# C-07_PWR_MGR.net
KiCad netlist of a schematic drawn in Altium Designer
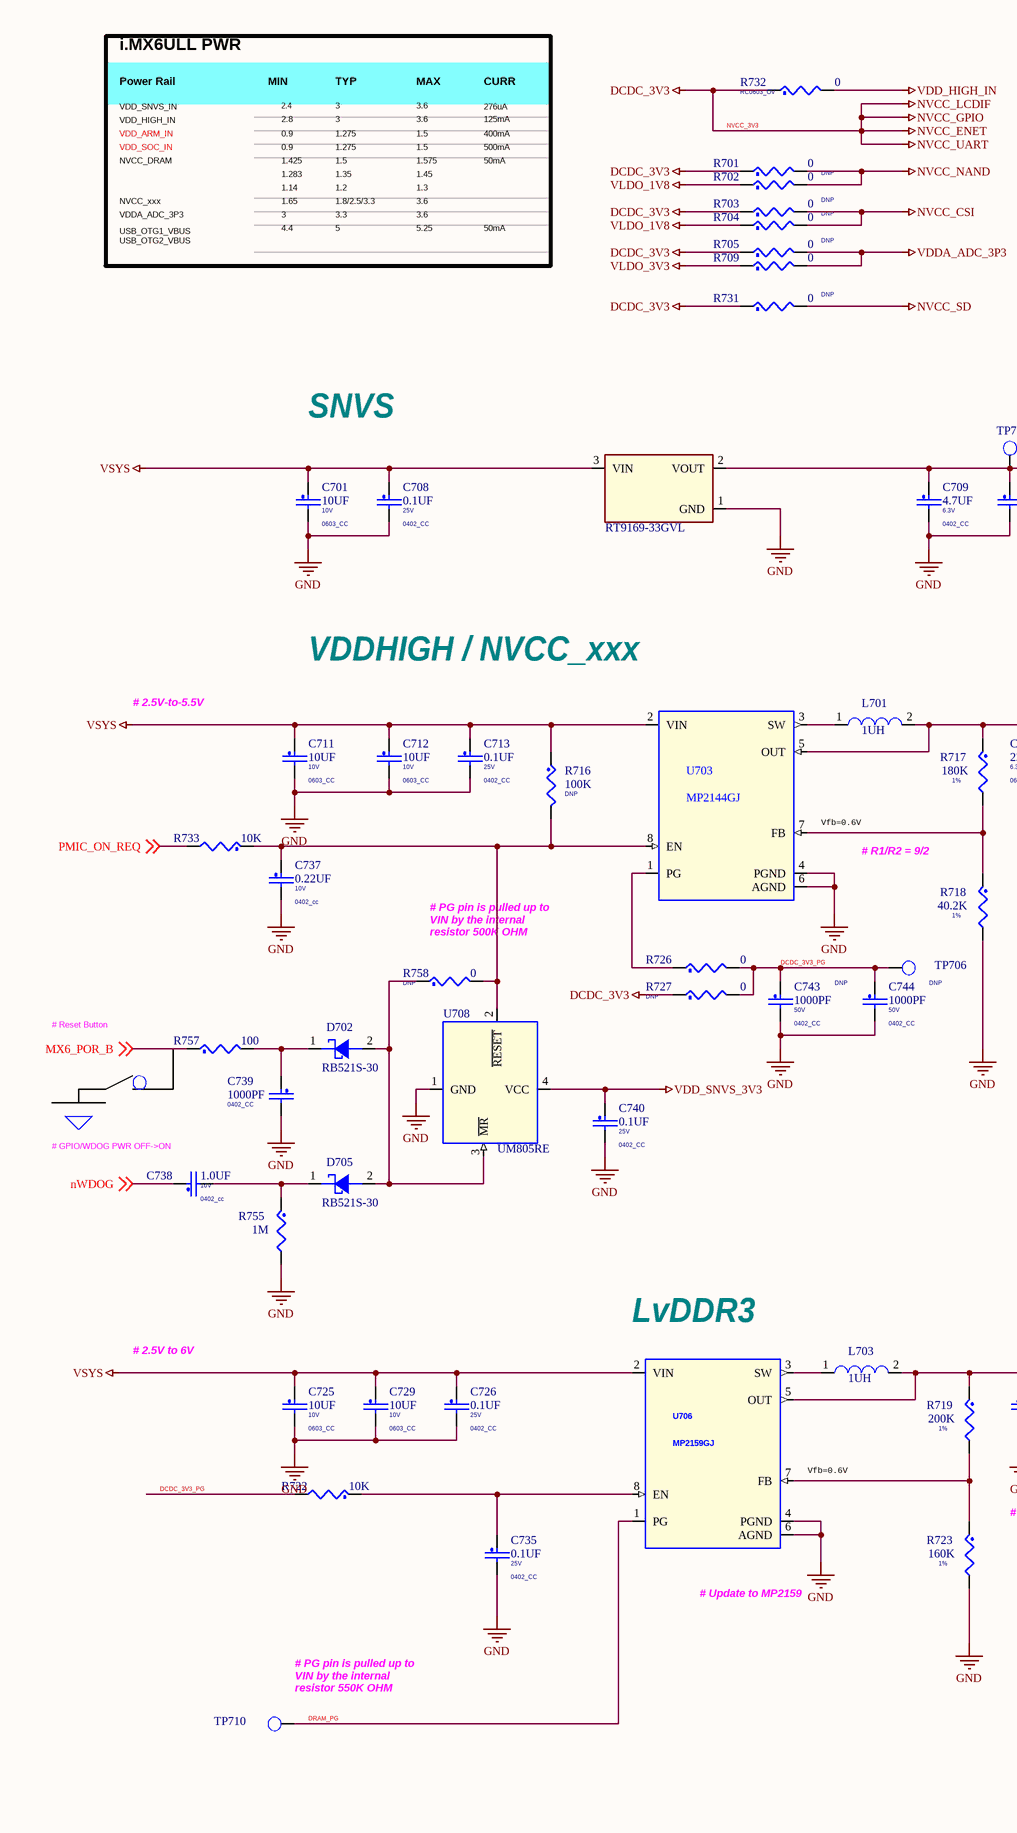
[diagram p0: C-07 PWR MGR.SchDoc, left]
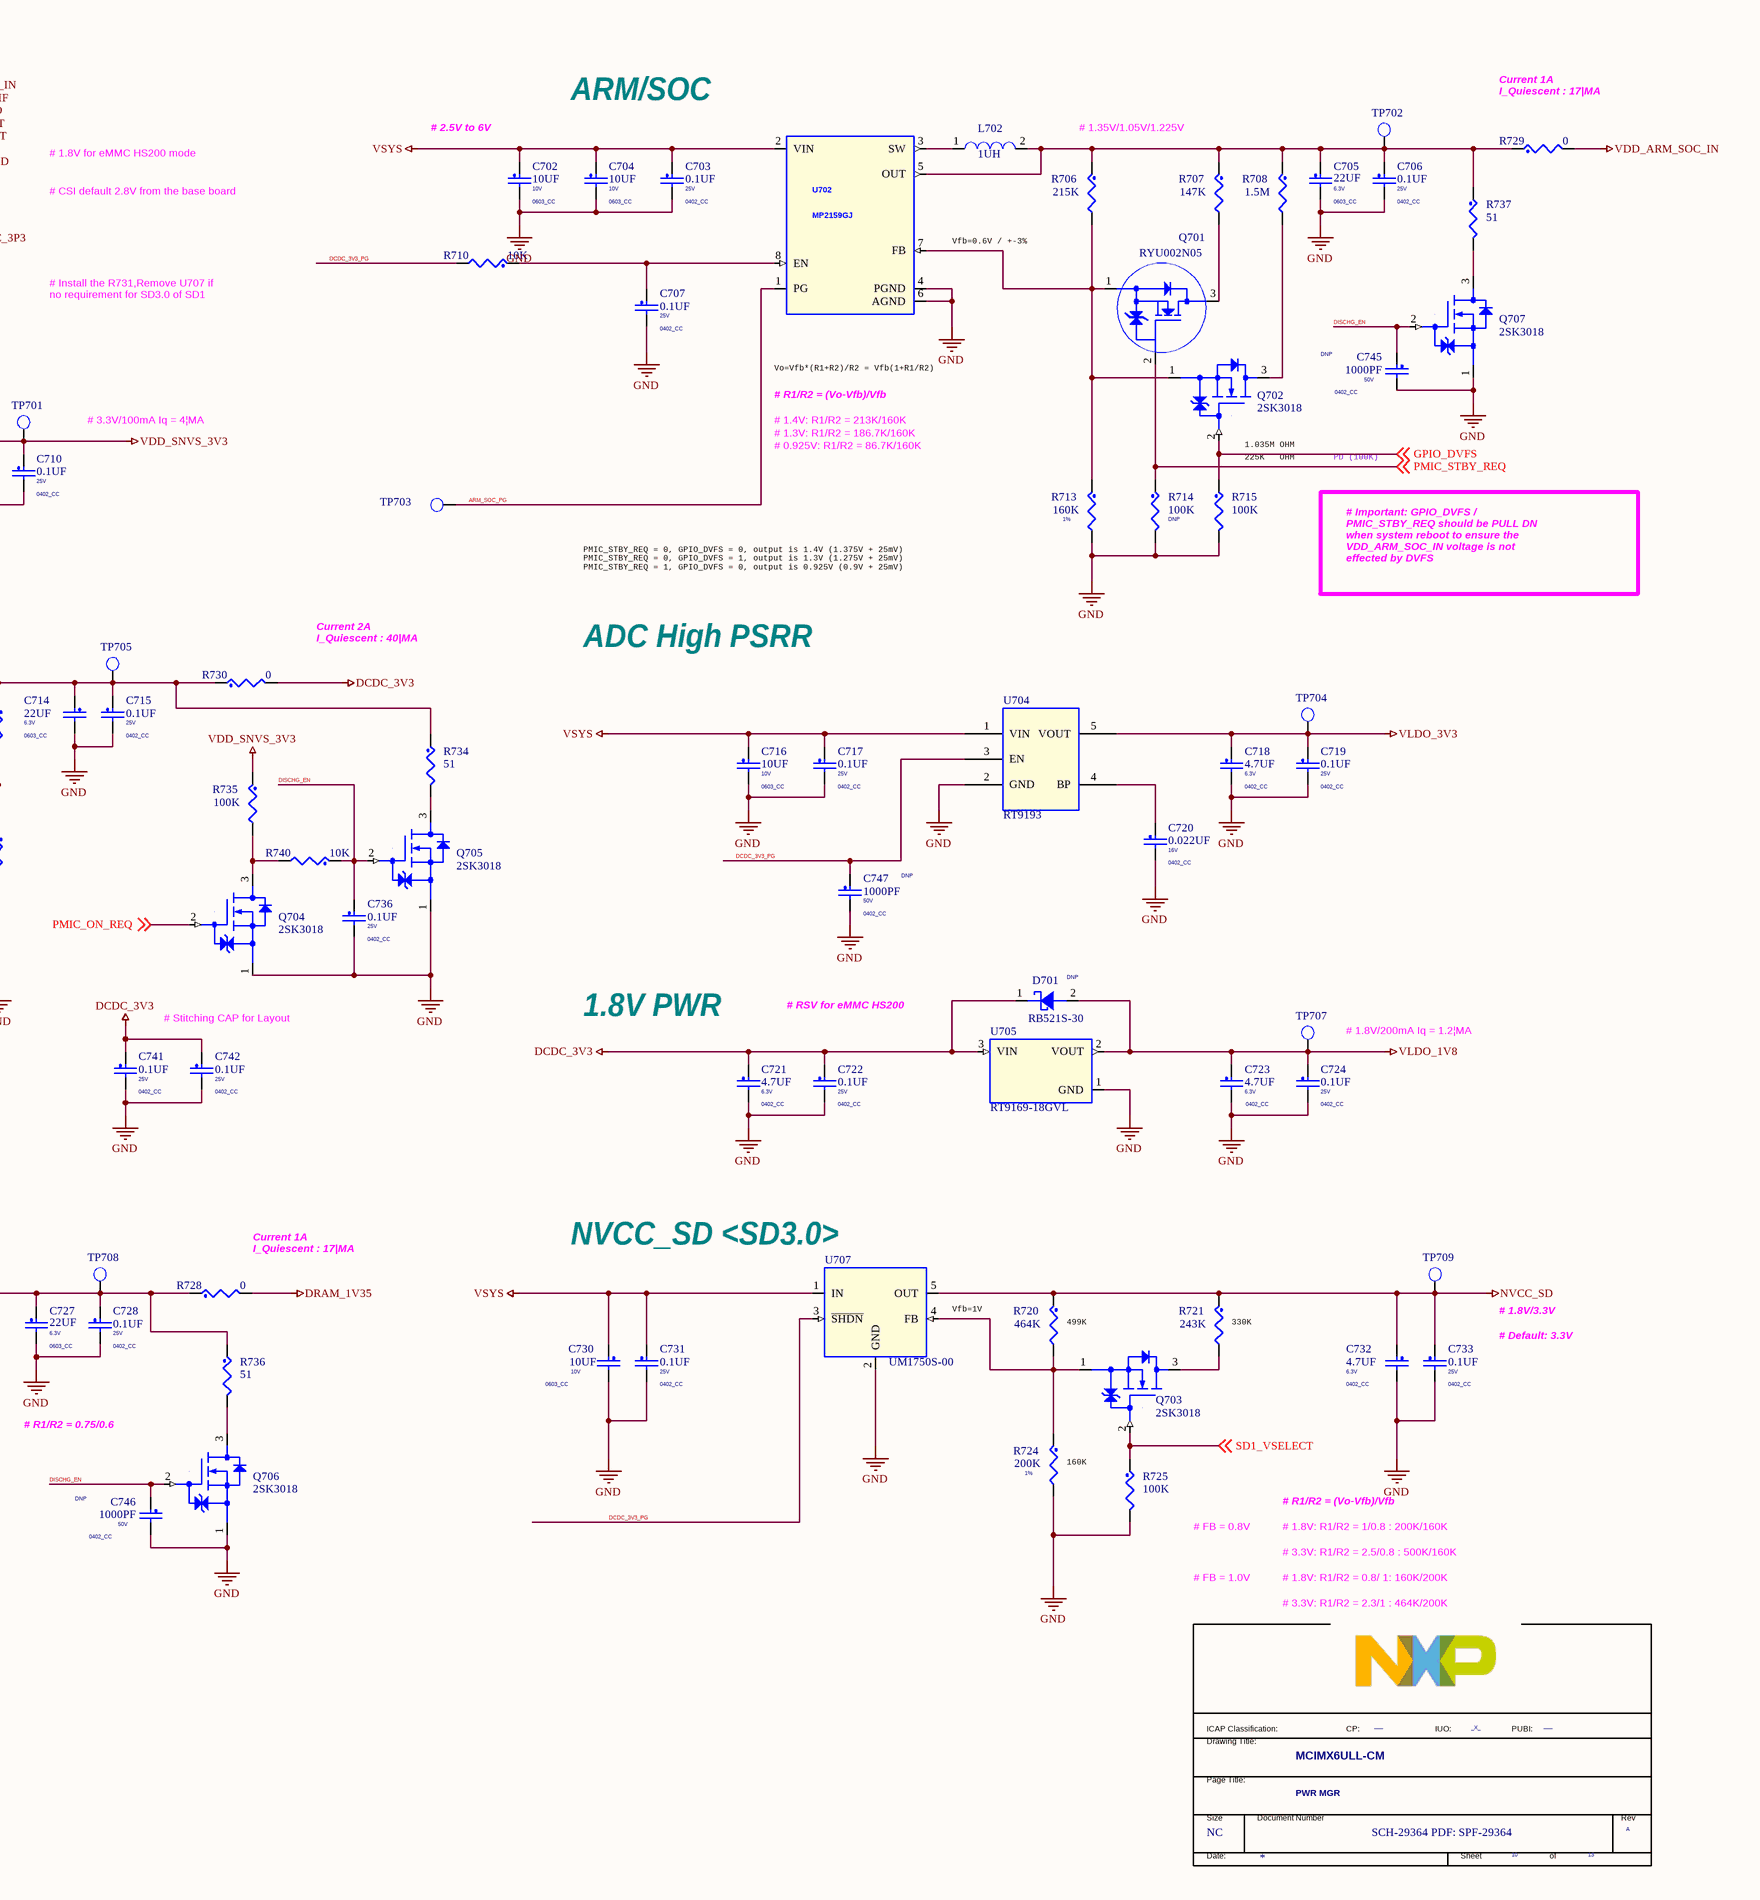
[diagram p1: C-07 PWR MGR.SchDoc, right]

(export (version "E")
  (design (tool "Eeschema 10.0.6"))
  (components
    (comp (ref "C701")
      (value "10UF")
      (footprint "C0603_H0.8mm")
      (description "CAP CER 10UF 10V 20% X5R 0603")
      (fields (field (name "PCB FOOTPRINT") "0603_CC") (field (name "VOLTAGE") "10V"))
      (libsource (lib "*") (part "CAP_NP"))
    )
    (comp (ref "C702")
      (value "10UF")
      (footprint "C0603_H0.8mm")
      (description "CAP CER 10UF 10V 20% X5R 0603")
      (fields (field (name "PCB FOOTPRINT") "0603_CC") (field (name "VOLTAGE") "10V"))
      (libsource (lib "*") (part "CAP_NP"))
    )
    (comp (ref "C703")
      (value "0.1UF")
      (footprint "C0402_H0.5mm")
      (description "CAP CER 0.1UF 25V 10% X5R 0402")
      (fields
        (field (name "PCB FOOTPRINT") "0402_CC")
        (field (name "TOLERANCE") "10%")
        (field (name "VOLTAGE") "25V")
      )
      (libsource (lib "*") (part "CAP_NP"))
    )
    (comp (ref "C704")
      (value "10UF")
      (footprint "C0603_H0.8mm")
      (description "CAP CER 10UF 10V 20% X5R 0603")
      (fields (field (name "PCB FOOTPRINT") "0603_CC") (field (name "VOLTAGE") "10V"))
      (libsource (lib "*") (part "CAP_NP"))
    )
    (comp (ref "C705")
      (value "22UF")
      (footprint "C0603_H0.8mm")
      (description "CAP CER 22UF 6.3V 20% X5R 0603")
      (fields
        (field (name "VOLTAGE RATING") "6.3V")
        (field (name "TOLERANCE") "20%")
        (field (name "VOLTAGE") "6.3V")
        (field (name "PCB FOOTPRINT") "0603_CC")
      )
      (libsource (lib "*") (part "CAP_NP"))
    )
    (comp (ref "C706")
      (value "0.1UF")
      (footprint "C0402_H0.5mm")
      (description "CAP CER 0.1UF 25V 10% X5R 0402")
      (fields
        (field (name "PCB FOOTPRINT") "0402_CC")
        (field (name "VOLTAGE") "25V")
        (field (name "TOLERANCE") "10%")
      )
      (libsource (lib "*") (part "CAP_NP"))
    )
    (comp (ref "C707")
      (value "0.1UF")
      (footprint "C0402_H0.5mm")
      (description "CAP CER 0.1UF 25V 10% X5R 0402")
      (fields
        (field (name "PCB FOOTPRINT") "0402_CC")
        (field (name "VOLTAGE") "25V")
        (field (name "TOLERANCE") "10%")
      )
      (libsource (lib "*") (part "CAP_NP"))
    )
    (comp (ref "C708")
      (value "0.1UF")
      (footprint "C0402_H0.5mm")
      (description "CAP CER 0.1UF 25V 10% X5R 0402")
      (fields
        (field (name "PCB FOOTPRINT") "0402_CC")
        (field (name "VOLTAGE") "25V")
        (field (name "TOLERANCE") "10%")
      )
      (libsource (lib "*") (part "CAP_NP"))
    )
    (comp (ref "C709")
      (value "4.7UF")
      (footprint "C0402_H0.5mm")
      (description "CAP CER 4.7UF 6.3V 20% X5R 0402")
      (fields
        (field (name "VOLTAGE") "6.3V")
        (field (name "VOLTAGE RATING") "6.3V")
        (field (name "TOLERANCE") "20%")
        (field (name "PCB FOOTPRINT") "0402_CC")
      )
      (libsource (lib "*") (part "CAP_NP"))
    )
    (comp (ref "C710")
      (value "0.1UF")
      (footprint "C0402_H0.5mm")
      (description "CAP CER 0.1UF 25V 10% X5R 0402")
      (fields
        (field (name "PCB FOOTPRINT") "0402_CC")
        (field (name "TOLERANCE") "10%")
        (field (name "VOLTAGE") "25V")
      )
      (libsource (lib "*") (part "CAP_NP"))
    )
    (comp (ref "C711")
      (value "10UF")
      (footprint "C0603_H0.8mm")
      (description "CAP CER 10UF 10V 20% X5R 0603")
      (fields (field (name "PCB FOOTPRINT") "0603_CC") (field (name "VOLTAGE") "10V"))
      (libsource (lib "*") (part "CAP_NP"))
    )
    (comp (ref "C712")
      (value "10UF")
      (footprint "C0603_H0.8mm")
      (description "CAP CER 10UF 10V 20% X5R 0603")
      (fields (field (name "PCB FOOTPRINT") "0603_CC") (field (name "VOLTAGE") "10V"))
      (libsource (lib "*") (part "CAP_NP"))
    )
    (comp (ref "C713")
      (value "0.1UF")
      (footprint "C0402_H0.5mm")
      (description "CAP CER 0.1UF 25V 10% X5R 0402")
      (fields
        (field (name "PCB FOOTPRINT") "0402_CC")
        (field (name "TOLERANCE") "10%")
        (field (name "VOLTAGE") "25V")
      )
      (libsource (lib "*") (part "CAP_NP"))
    )
    (comp (ref "C714")
      (value "22UF")
      (footprint "C0603_H0.8mm")
      (description "CAP CER 22UF 6.3V 20% X5R 0603")
      (fields
        (field (name "PCB FOOTPRINT") "0603_CC")
        (field (name "VOLTAGE RATING") "6.3V")
        (field (name "TOLERANCE") "20%")
        (field (name "VOLTAGE") "6.3V")
      )
      (libsource (lib "*") (part "CAP_NP"))
    )
    (comp (ref "C715")
      (value "0.1UF")
      (footprint "C0402_H0.5mm")
      (description "CAP CER 0.1UF 25V 10% X5R 0402")
      (fields
        (field (name "PCB FOOTPRINT") "0402_CC")
        (field (name "VOLTAGE") "25V")
        (field (name "TOLERANCE") "10%")
      )
      (libsource (lib "*") (part "CAP_NP"))
    )
    (comp (ref "C716")
      (value "10UF")
      (footprint "C0603_H0.8mm")
      (description "CAP CER 10UF 10V 20% X5R 0603")
      (fields (field (name "PCB FOOTPRINT") "0603_CC") (field (name "VOLTAGE") "10V"))
      (libsource (lib "*") (part "CAP_NP"))
    )
    (comp (ref "C717")
      (value "0.1UF")
      (footprint "C0402_H0.5mm")
      (description "CAP CER 0.1UF 25V 10% X5R 0402")
      (fields
        (field (name "PCB FOOTPRINT") "0402_CC")
        (field (name "TOLERANCE") "10%")
        (field (name "VOLTAGE") "25V")
      )
      (libsource (lib "*") (part "CAP_NP"))
    )
    (comp (ref "C718")
      (value "4.7UF")
      (footprint "C0402_H0.5mm")
      (description "CAP CER 4.7UF 6.3V 20% X5R 0402")
      (fields
        (field (name "TOLERANCE") "20%")
        (field (name "VOLTAGE RATING") "6.3V")
        (field (name "VOLTAGE") "6.3V")
        (field (name "PCB FOOTPRINT") "0402_CC")
      )
      (libsource (lib "*") (part "CAP_NP"))
    )
    (comp (ref "C719")
      (value "0.1UF")
      (footprint "C0402_H0.5mm")
      (description "CAP CER 0.1UF 25V 10% X5R 0402")
      (fields
        (field (name "PCB FOOTPRINT") "0402_CC")
        (field (name "VOLTAGE") "25V")
        (field (name "TOLERANCE") "10%")
      )
      (libsource (lib "*") (part "CAP_NP"))
    )
    (comp (ref "C720")
      (value "0.022UF")
      (footprint "C0402_H0.5mm")
      (description "CAP CER 0.022UF 16V 10% X7R 0402")
      (fields
        (field (name "TOLERANCE") "10%")
        (field (name "VOLTAGE") "16V")
        (field (name "PCB FOOTPRINT") "0402_CC")
      )
      (libsource (lib "*") (part "CAP_NP"))
    )
    (comp (ref "C721")
      (value "4.7UF")
      (footprint "C0402_H0.5mm")
      (description "CAP CER 4.7UF 6.3V 20% X5R 0402")
      (fields
        (field (name "VOLTAGE") "6.3V")
        (field (name "VOLTAGE RATING") "6.3V")
        (field (name "TOLERANCE") "20%")
        (field (name "PCB FOOTPRINT") "0402_CC")
      )
      (libsource (lib "*") (part "CAP_NP"))
    )
    (comp (ref "C722")
      (value "0.1UF")
      (footprint "C0402_H0.5mm")
      (description "CAP CER 0.1UF 25V 10% X5R 0402")
      (fields
        (field (name "PCB FOOTPRINT") "0402_CC")
        (field (name "VOLTAGE") "25V")
        (field (name "TOLERANCE") "10%")
      )
      (libsource (lib "*") (part "CAP_NP"))
    )
    (comp (ref "C723")
      (value "4.7UF")
      (footprint "C0402_H0.5mm")
      (description "CAP CER 4.7UF 6.3V 20% X5R 0402")
      (fields
        (field (name "TOLERANCE") "20%")
        (field (name "VOLTAGE RATING") "6.3V")
        (field (name "VOLTAGE") "6.3V")
        (field (name "PCB FOOTPRINT") "0402_CC")
      )
      (libsource (lib "*") (part "CAP_NP"))
    )
    (comp (ref "C724")
      (value "0.1UF")
      (footprint "C0402_H0.5mm")
      (description "CAP CER 0.1UF 25V 10% X5R 0402")
      (fields
        (field (name "PCB FOOTPRINT") "0402_CC")
        (field (name "TOLERANCE") "10%")
        (field (name "VOLTAGE") "25V")
      )
      (libsource (lib "*") (part "CAP_NP"))
    )
    (comp (ref "C725")
      (value "10UF")
      (footprint "C0603_H0.8mm")
      (description "CAP CER 10UF 10V 20% X5R 0603")
      (fields (field (name "PCB FOOTPRINT") "0603_CC") (field (name "VOLTAGE") "10V"))
      (libsource (lib "*") (part "CAP_NP"))
    )
    (comp (ref "C726")
      (value "0.1UF")
      (footprint "C0402_H0.5mm")
      (description "CAP CER 0.1UF 25V 10% X5R 0402")
      (fields
        (field (name "PCB FOOTPRINT") "0402_CC")
        (field (name "TOLERANCE") "10%")
        (field (name "VOLTAGE") "25V")
      )
      (libsource (lib "*") (part "CAP_NP"))
    )
    (comp (ref "C727")
      (value "22UF")
      (footprint "C0603_H0.8mm")
      (description "CAP CER 22UF 6.3V 20% X5R 0603")
      (fields
        (field (name "VOLTAGE RATING") "6.3V")
        (field (name "TOLERANCE") "20%")
        (field (name "VOLTAGE") "6.3V")
        (field (name "PCB FOOTPRINT") "0603_CC")
      )
      (libsource (lib "*") (part "CAP_NP"))
    )
    (comp (ref "C728")
      (value "0.1UF")
      (footprint "C0402_H0.5mm")
      (description "CAP CER 0.1UF 25V 10% X5R 0402")
      (fields
        (field (name "PCB FOOTPRINT") "0402_CC")
        (field (name "TOLERANCE") "10%")
        (field (name "VOLTAGE") "25V")
      )
      (libsource (lib "*") (part "CAP_NP"))
    )
    (comp (ref "C729")
      (value "10UF")
      (footprint "C0603_H0.8mm")
      (description "CAP CER 10UF 10V 20% X5R 0603")
      (fields (field (name "PCB FOOTPRINT") "0603_CC") (field (name "VOLTAGE") "10V"))
      (libsource (lib "*") (part "CAP_NP"))
    )
    (comp (ref "C730")
      (value "10UF")
      (footprint "C0603_H0.8mm")
      (description "CAP CER 10UF 10V 20% X5R 0603")
      (fields (field (name "PCB FOOTPRINT") "0603_CC") (field (name "VOLTAGE") "10V"))
      (libsource (lib "*") (part "CAP_NP"))
    )
    (comp (ref "C731")
      (value "0.1UF")
      (footprint "C0402_H0.5mm")
      (description "CAP CER 0.1UF 25V 10% X5R 0402")
      (fields
        (field (name "PCB FOOTPRINT") "0402_CC")
        (field (name "VOLTAGE") "25V")
        (field (name "TOLERANCE") "10%")
      )
      (libsource (lib "*") (part "CAP_NP"))
    )
    (comp (ref "C732")
      (value "4.7UF")
      (footprint "C0402_H0.5mm")
      (description "CAP CER 4.7UF 6.3V 20% X5R 0402")
      (fields
        (field (name "PCB FOOTPRINT") "0402_CC")
        (field (name "VOLTAGE") "6.3V")
        (field (name "VOLTAGE RATING") "6.3V")
        (field (name "TOLERANCE") "20%")
      )
      (libsource (lib "*") (part "CAP_NP"))
    )
    (comp (ref "C733")
      (value "0.1UF")
      (footprint "C0402_H0.5mm")
      (description "CAP CER 0.1UF 25V 10% X5R 0402")
      (fields
        (field (name "PCB FOOTPRINT") "0402_CC")
        (field (name "VOLTAGE") "25V")
        (field (name "TOLERANCE") "10%")
      )
      (libsource (lib "*") (part "CAP_NP"))
    )
    (comp (ref "C735")
      (value "0.1UF")
      (footprint "C0402_H0.5mm")
      (description "CAP CER 0.1UF 25V 10% X5R 0402")
      (fields
        (field (name "PCB FOOTPRINT") "0402_CC")
        (field (name "TOLERANCE") "10%")
        (field (name "VOLTAGE") "25V")
      )
      (libsource (lib "*") (part "CAP_NP"))
    )
    (comp (ref "C736")
      (value "0.1UF")
      (footprint "C0402_H0.5mm")
      (description "CAP CER 0.1UF 25V 10% X5R 0402")
      (fields
        (field (name "PCB FOOTPRINT") "0402_CC")
        (field (name "VOLTAGE") "25V")
        (field (name "TOLERANCE") "10%")
      )
      (libsource (lib "*") (part "CAP_NP"))
    )
    (comp (ref "C737")
      (value "0.22UF")
      (footprint "C0402_H0.5mm")
      (description "CAP CER 0.22UF 10V 10% X5R 0402")
      (fields
        (field (name "PCB FOOTPRINT") "0402_cc")
        (field (name "TOLERANCE") "10%")
        (field (name "VOLTAGE") "10V")
      )
      (libsource (lib "*") (part "CAP_NP"))
    )
    (comp (ref "C738")
      (value "1.0UF")
      (footprint "C0402_H0.5mm")
      (description "CAP CER 1.0UF 10V 10% X5R 0402")
      (fields (field (name "PCB FOOTPRINT") "0402_cc") (field (name "VOLTAGE") "10V"))
      (libsource (lib "*") (part "CAP_NP"))
    )
    (comp (ref "C739")
      (value "1000PF")
      (footprint "C0402_H0.5mm")
      (description "CAP CER 1000PF 50V 5% C0G 0402")
      (fields
        (field (name "PCB FOOTPRINT") "0402_CC")
        (field (name "TOLERANCE") "5%")
        (field (name "VOLTAGE") "50V")
      )
      (libsource (lib "*") (part "CAP_NP"))
    )
    (comp (ref "C740")
      (value "0.1UF")
      (footprint "C0402_H0.5mm")
      (description "CAP CER 0.1UF 25V 10% X5R 0402")
      (fields
        (field (name "PCB FOOTPRINT") "0402_CC")
        (field (name "TOLERANCE") "10%")
        (field (name "VOLTAGE") "25V")
      )
      (libsource (lib "*") (part "CAP_NP"))
    )
    (comp (ref "C741")
      (value "0.1UF")
      (footprint "C0402_H0.5mm")
      (description "CAP CER 0.1UF 25V 10% X5R 0402")
      (fields
        (field (name "PCB FOOTPRINT") "0402_CC")
        (field (name "VOLTAGE") "25V")
        (field (name "TOLERANCE") "10%")
      )
      (libsource (lib "*") (part "CAP_NP"))
    )
    (comp (ref "C742")
      (value "0.1UF")
      (footprint "C0402_H0.5mm")
      (description "CAP CER 0.1UF 25V 10% X5R 0402")
      (fields
        (field (name "PCB FOOTPRINT") "0402_CC")
        (field (name "TOLERANCE") "10%")
        (field (name "VOLTAGE") "25V")
      )
      (libsource (lib "*") (part "CAP_NP"))
    )
    (comp (ref "C743")
      (value "1000PF")
      (footprint "C0402_H0.5mm")
      (description "CAP CER 1000PF 50V 5% C0G 0402")
      (fields
        (field (name "PCB FOOTPRINT") "0402_CC")
        (field (name "VOLTAGE") "50V")
        (field (name "ASSY_OPT") "DNP")
        (field (name "TOLERANCE") "5%")
      )
      (libsource (lib "*") (part "CAP_NP"))
    )
    (comp (ref "C744")
      (value "1000PF")
      (footprint "C0402_H0.5mm")
      (description "CAP CER 1000PF 50V 5% C0G 0402")
      (fields
        (field (name "PCB FOOTPRINT") "0402_CC")
        (field (name "TOLERANCE") "5%")
        (field (name "ASSY_OPT") "DNP")
        (field (name "VOLTAGE") "50V")
      )
      (libsource (lib "*") (part "CAP_NP"))
    )
    (comp (ref "C745")
      (value "1000PF")
      (footprint "C0402_H0.5mm")
      (description "CAP CER 1000PF 50V 5% C0G 0402")
      (fields
        (field (name "PCB FOOTPRINT") "0402_CC")
        (field (name "TOLERANCE") "5%")
        (field (name "ASSY_OPT") "DNP")
        (field (name "VOLTAGE") "50V")
      )
      (libsource (lib "*") (part "CAP_NP"))
    )
    (comp (ref "C746")
      (value "1000PF")
      (footprint "C0402_H0.5mm")
      (description "CAP CER 1000PF 50V 5% C0G 0402")
      (fields
        (field (name "PCB FOOTPRINT") "0402_CC")
        (field (name "TOLERANCE") "5%")
        (field (name "ASSY_OPT") "DNP")
        (field (name "VOLTAGE") "50V")
      )
      (libsource (lib "*") (part "CAP_NP"))
    )
    (comp (ref "C747")
      (value "1000PF")
      (footprint "C0402_H0.5mm")
      (description "CAP CER 1000PF 50V 5% C0G 0402")
      (fields
        (field (name "PCB FOOTPRINT") "0402_CC")
        (field (name "TOLERANCE") "5%")
        (field (name "ASSY_OPT") "DNP")
        (field (name "VOLTAGE") "50V")
      )
      (libsource (lib "*") (part "CAP_NP"))
    )
    (comp (ref "D701")
      (value "RB521S-30")
      (footprint "SOD-523_1.2x0.8mm")
      (description "DIODE SCH 200MA 30V SOD-523")
      (fields (field (name "ASSY_OPT") "DNP"))
      (libsource (lib "*") (part "DIODE_SCHTKY"))
    )
    (comp (ref "D702")
      (value "RB521S-30")
      (footprint "SOD-523_1.2x0.8mm")
      (description "DIODE SCH 200MA 30V SOD-523")
      (libsource (lib "*") (part "DIODE_SCHTKY"))
    )
    (comp (ref "D705")
      (value "RB521S-30")
      (footprint "SOD-523_1.2x0.8mm")
      (description "DIODE SCH 200MA 30V SOD-523")
      (libsource (lib "*") (part "DIODE_SCHTKY"))
    )
    (comp (ref "L701")
      (value "1UH")
      (footprint "SWPA4020S")
      (description "IND PWR 1UH@100KHZ 2.6A 30% SMT")
      (libsource (lib "*") (part "IND"))
    )
    (comp (ref "L702")
      (value "1UH")
      (footprint "SWPA4020S")
      (description "IND PWR 1UH@100KHZ 2.6A 30% SMT")
      (libsource (lib "*") (part "IND"))
    )
    (comp (ref "L703")
      (value "1UH")
      (footprint "SWPA4020S")
      (description "IND PWR 1UH@100KHZ 2.6A 30% SMT")
      (libsource (lib "*") (part "IND"))
    )
    (comp (ref "Q701")
      (value "RYU002N05")
      (footprint "SOT323-3")
      (description "TRAN NMOS SW 0.9V DRIVE 50V UMT3")
      (libsource (lib "*") (part "NMOSFET_3P_ESD_DIODE"))
    )
    (comp (ref "Q702")
      (value "2SK3018")
      (footprint "SOT323-3")
      (description "TRANS MOSFET N-CH 30V .1A SOT-323")
      (libsource (lib "*") (part "2SK3018"))
    )
    (comp (ref "Q703")
      (value "2SK3018")
      (footprint "SOT323-3")
      (description "TRANS MOSFET N-CH 30V .1A SOT-323")
      (libsource (lib "*") (part "2SK3018"))
    )
    (comp (ref "Q704")
      (value "2SK3018")
      (footprint "SOT323-3")
      (description "TRANS MOSFET N-CH 30V .1A SOT-323")
      (libsource (lib "*") (part "2SK3018"))
    )
    (comp (ref "Q705")
      (value "2SK3018")
      (footprint "SOT323-3")
      (description "TRANS MOSFET N-CH 30V .1A SOT-323")
      (libsource (lib "*") (part "2SK3018"))
    )
    (comp (ref "Q706")
      (value "2SK3018")
      (footprint "SOT323-3")
      (description "TRANS MOSFET N-CH 30V .1A SOT-323")
      (libsource (lib "*") (part "2SK3018"))
    )
    (comp (ref "Q707")
      (value "2SK3018")
      (footprint "SOT323-3")
      (description "TRANS MOSFET N-CH 30V .1A SOT-323")
      (libsource (lib "*") (part "2SK3018"))
    )
    (comp (ref "R701")
      (value "0")
      (footprint "R0402_H0.35mm")
      (description "RES MF ZERO OHM 1/16W 5% 0402")
      (fields (field (name "TOLERANCE") "5%"))
      (libsource (lib "*") (part "RES"))
    )
    (comp (ref "R702")
      (value "0")
      (footprint "R0402_H0.35mm")
      (description "RES MF ZERO OHM 1/16W 5% 0402")
      (fields (field (name "TOLERANCE") "5%") (field (name "ASSY_OPT") "DNP"))
      (libsource (lib "*") (part "RES"))
    )
    (comp (ref "R703")
      (value "0")
      (footprint "R0402_H0.35mm")
      (description "RES MF ZERO OHM 1/16W 5% 0402")
      (fields (field (name "TOLERANCE") "5%") (field (name "ASSY_OPT") "DNP"))
      (libsource (lib "*") (part "RES"))
    )
    (comp (ref "R704")
      (value "0")
      (footprint "R0402_H0.35mm")
      (description "RES MF ZERO OHM 1/16W 5% 0402")
      (fields (field (name "ASSY_OPT") "DNP") (field (name "TOLERANCE") "5%"))
      (libsource (lib "*") (part "RES"))
    )
    (comp (ref "R705")
      (value "0")
      (footprint "R0402_H0.35mm")
      (description "RES MF ZERO OHM 1/16W 5% 0402")
      (fields (field (name "ASSY_OPT") "DNP") (field (name "TOLERANCE") "5%"))
      (libsource (lib "*") (part "RES"))
    )
    (comp (ref "R706")
      (value "215K")
      (footprint "R0402_H0.35mm")
      (description "RES MF 215K  1/16W 1% 0402")
      (fields (field (name "TOLERANCE") "1%"))
      (libsource (lib "*") (part "RES"))
    )
    (comp (ref "R707")
      (value "147K")
      (footprint "R0402_H0.35mm")
      (description "RES MF 147K  1/16W 1% 0402")
      (fields (field (name "TOLERANCE") "1%"))
      (libsource (lib "*") (part "RES"))
    )
    (comp (ref "R708")
      (value "1.5M")
      (footprint "R0402_H0.35mm")
      (description "RES MF 1.5M  1/16W 1% 0402")
      (fields (field (name "TOLERANCE") "1%"))
      (libsource (lib "*") (part "RES"))
    )
    (comp (ref "R709")
      (value "0")
      (footprint "R0402_H0.35mm")
      (description "RES MF ZERO OHM 1/16W 5% 0402")
      (fields (field (name "TOLERANCE") "5%"))
      (libsource (lib "*") (part "RES"))
    )
    (comp (ref "R710")
      (value "10K")
      (footprint "R0402_H0.35mm")
      (description "RES MF 10K 1/16W 5% 0402")
      (fields (field (name "TOLERANCE") "5%"))
      (libsource (lib "*") (part "RES"))
    )
    (comp (ref "R713")
      (value "160K")
      (footprint "R0402_H0.35mm")
      (description "RES MF 160K  1/16W 1% 0402")
      (fields (field (name "TOLERANCE") "1%"))
      (libsource (lib "*") (part "RES"))
    )
    (comp (ref "R714")
      (value "100K")
      (footprint "R0402_H0.35mm")
      (description "RES MF 100K 1/16W 5% 0402")
      (fields (field (name "ASSY_OPT") "DNP") (field (name "TOLERANCE") "5%"))
      (libsource (lib "*") (part "RES"))
    )
    (comp (ref "R715")
      (value "100K")
      (footprint "R0402_H0.35mm")
      (description "RES MF 100K 1/16W 5% 0402")
      (fields (field (name "TOLERANCE") "5%"))
      (libsource (lib "*") (part "RES"))
    )
    (comp (ref "R716")
      (value "100K")
      (footprint "R0402_H0.35mm")
      (description "RES MF 100K 1/16W 5% 0402")
      (fields (field (name "TOLERANCE") "5%") (field (name "ASSY_OPT") "DNP"))
      (libsource (lib "*") (part "RES"))
    )
    (comp (ref "R717")
      (value "180K")
      (footprint "R0402_H0.35mm")
      (description "RES MF 180K  1/16W 1% 0402")
      (fields (field (name "TOLERANCE") "1%"))
      (libsource (lib "*") (part "RES"))
    )
    (comp (ref "R718")
      (value "40.2K")
      (footprint "R0402_H0.35mm")
      (description "RES MF 40.2K  1/16W 1% 0402")
      (fields (field (name "TOLERANCE") "1%"))
      (libsource (lib "*") (part "RES"))
    )
    (comp (ref "R719")
      (value "200K")
      (footprint "R0402_H0.35mm")
      (description "RES MF 200K  1/16W 1% 0402")
      (fields (field (name "TOLERANCE") "1%"))
      (libsource (lib "*") (part "RES"))
    )
    (comp (ref "R720")
      (value "464K")
      (footprint "R0402_H0.35mm")
      (description "RES MF 464K  1/16W 1% 0402")
      (fields (field (name "TOLERANCE") "1%"))
      (libsource (lib "*") (part "RES"))
    )
    (comp (ref "R721")
      (value "243K")
      (footprint "R0402_H0.35mm")
      (description "RES MF 243K  1/16W 1% 0402")
      (fields (field (name "TOLERANCE") "1%"))
      (libsource (lib "*") (part "RES"))
    )
    (comp (ref "R722")
      (value "10K")
      (footprint "R0402_H0.35mm")
      (description "RES MF 10K 1/16W 5% 0402")
      (fields (field (name "TOLERANCE") "5%"))
      (libsource (lib "*") (part "RES"))
    )
    (comp (ref "R723")
      (value "160K")
      (footprint "R0402_H0.35mm")
      (description "RES MF 160K  1/16W 1% 0402")
      (fields (field (name "TOLERANCE") "1%"))
      (libsource (lib "*") (part "RES"))
    )
    (comp (ref "R724")
      (value "200K")
      (footprint "R0402_H0.35mm")
      (description "RES MF 200K  1/16W 1% 0402")
      (fields (field (name "TOLERANCE") "1%"))
      (libsource (lib "*") (part "RES"))
    )
    (comp (ref "R725")
      (value "100K")
      (footprint "R0402_H0.35mm")
      (description "RES MF 100K 1/16W 5% 0402")
      (fields (field (name "TOLERANCE") "5%"))
      (libsource (lib "*") (part "RES"))
    )
    (comp (ref "R726")
      (value "0")
      (footprint "R0402_H0.35mm")
      (description "RES MF ZERO OHM 1/16W 5% 0402")
      (fields (field (name "TOLERANCE") "5%"))
      (libsource (lib "*") (part "RES"))
    )
    (comp (ref "R727")
      (value "0")
      (footprint "R0402_H0.35mm")
      (description "RES MF ZERO OHM 1/16W 5% 0402")
      (fields (field (name "ASSY_OPT") "DNP") (field (name "TOLERANCE") "5%"))
      (libsource (lib "*") (part "RES"))
    )
    (comp (ref "R728")
      (value "0")
      (footprint "R0805_H0.5mm")
      (description "RES MF ZERO OHM 1/8W -- 0805")
      (fields (field (name "TOLERANCE") "5%"))
      (libsource (lib "*") (part "RES"))
    )
    (comp (ref "R729")
      (value "0")
      (footprint "R0805_H0.5mm")
      (description "RES MF ZERO OHM 1/8W -- 0805")
      (fields (field (name "TOLERANCE") "5%"))
      (libsource (lib "*") (part "RES"))
    )
    (comp (ref "R730")
      (value "0")
      (footprint "R0805_H0.5mm")
      (description "RES MF ZERO OHM 1/8W -- 0805")
      (fields (field (name "TOLERANCE") "5%"))
      (libsource (lib "*") (part "RES"))
    )
    (comp (ref "R731")
      (value "0")
      (footprint "R0402_H0.35mm")
      (description "RES MF ZERO OHM 1/16W 5% 0402")
      (fields (field (name "ASSY_OPT") "DNP") (field (name "TOLERANCE") "5%"))
      (libsource (lib "*") (part "RES"))
    )
    (comp (ref "R732")
      (value "0")
      (footprint "R0603_H0.45mm")
      (description "RES MF ZERO OHM 1/10W -- 0603")
      (fields (field (name "PCB FOOTPRINT") "RC0603_OV"))
      (libsource (lib "*") (part "RES"))
    )
    (comp (ref "R733")
      (value "10K")
      (footprint "R0402_H0.35mm")
      (description "RES MF 10K 1/16W 5% 0402")
      (fields (field (name "TOLERANCE") "5%"))
      (libsource (lib "*") (part "RES"))
    )
    (comp (ref "R734")
      (value "51")
      (footprint "R0402_H0.35mm")
      (description "RES MF 51 OHM 1/16W 1% 0402")
      (fields (field (name "TOLERANCE") "1%"))
      (libsource (lib "*") (part "RES"))
    )
    (comp (ref "R735")
      (value "100K")
      (footprint "R0402_H0.35mm")
      (description "RES MF 100K 1/16W 5% 0402")
      (fields (field (name "TOLERANCE") "5%"))
      (libsource (lib "*") (part "RES"))
    )
    (comp (ref "R736")
      (value "51")
      (footprint "R0402_H0.35mm")
      (description "RES MF 51 OHM 1/16W 1% 0402")
      (fields (field (name "TOLERANCE") "1%"))
      (libsource (lib "*") (part "RES"))
    )
    (comp (ref "R737")
      (value "51")
      (footprint "R0402_H0.35mm")
      (description "RES MF 51 OHM 1/16W 1% 0402")
      (fields (field (name "TOLERANCE") "1%"))
      (libsource (lib "*") (part "RES"))
    )
    (comp (ref "R740")
      (value "10K")
      (footprint "R0402_H0.35mm")
      (description "RES MF 10K 1/16W 5% 0402")
      (fields (field (name "TOLERANCE") "5%"))
      (libsource (lib "*") (part "RES"))
    )
    (comp (ref "R755")
      (value "1M")
      (footprint "R0402_H0.35mm")
      (description "RES MF 1.0M 1/10W 5% 0402")
      (fields (field (name "TOLERANCE") "5%"))
      (libsource (lib "*") (part "RES"))
    )
    (comp (ref "R757")
      (value "100")
      (footprint "R0402_H0.35mm")
      (description "RES MF 100 OHM 1/16W 1% 0402")
      (fields (field (name "TOLERANCE") "1%"))
      (libsource (lib "*") (part "RES"))
    )
    (comp (ref "R758")
      (value "0")
      (footprint "R0402_H0.35mm")
      (description "RES MF ZERO OHM 1/16W 5% 0402")
      (fields (field (name "TOLERANCE") "5%") (field (name "ASSY_OPT") "DNP"))
      (libsource (lib "*") (part "RES"))
    )
    (comp (ref "TP701")
      (value "TP_35MIL")
      (footprint "TPAD_035")
      (description "TEST POINT PAD .035 SMT, no part to order")
      (libsource (lib "*") (part "T POINT R"))
    )
    (comp (ref "TP702")
      (value "TP_35MIL")
      (footprint "TPAD_035")
      (description "TEST POINT PAD .035 SMT, no part to order")
      (libsource (lib "*") (part "T POINT R"))
    )
    (comp (ref "TP703")
      (value "TP_35MIL")
      (footprint "TPAD_035")
      (description "TEST POINT PAD .035 SMT, no part to order")
      (libsource (lib "*") (part "T POINT R"))
    )
    (comp (ref "TP704")
      (value "TP_35MIL")
      (footprint "TPAD_035")
      (description "TEST POINT PAD .035 SMT, no part to order")
      (libsource (lib "*") (part "T POINT R"))
    )
    (comp (ref "TP705")
      (value "TP_35MIL")
      (footprint "TPAD_035")
      (description "TEST POINT PAD .035 SMT, no part to order")
      (libsource (lib "*") (part "T POINT R"))
    )
    (comp (ref "TP706")
      (value "TP_35MIL")
      (footprint "TPAD_035")
      (description "TEST POINT PAD .035 SMT, no part to order")
      (libsource (lib "*") (part "T POINT R"))
    )
    (comp (ref "TP707")
      (value "TP_35MIL")
      (footprint "TPAD_035")
      (description "TEST POINT PAD .035 SMT, no part to order")
      (libsource (lib "*") (part "T POINT R"))
    )
    (comp (ref "TP708")
      (value "TP_35MIL")
      (footprint "TPAD_035")
      (description "TEST POINT PAD .035 SMT, no part to order")
      (libsource (lib "*") (part "T POINT R"))
    )
    (comp (ref "TP709")
      (value "TP_35MIL")
      (footprint "TPAD_035")
      (description "TEST POINT PAD .035 SMT, no part to order")
      (libsource (lib "*") (part "T POINT R"))
    )
    (comp (ref "TP710")
      (value "TP_35MIL")
      (footprint "TPAD_035")
      (description "TEST POINT PAD .035 SMT, no part to order")
      (libsource (lib "*") (part "T POINT R"))
    )
    (comp (ref "U701")
      (value "RT9169-33GVL")
      (footprint "SOT23-3")
      (description "IC VREG LDO 3.3V 100mA 2-6V SOT-23-3")
      (libsource (lib "*") (part "RT9169_3P"))
    )
    (comp (ref "U702")
      (value "MP2159GJ")
      (footprint "TSOT23-8_3x1.7mm")
      (description "IC VREG SYNC SW 0.6V 1A 2.5-6V TSOT23-8")
      (libsource (lib "*") (part "MP2159GJ_8P"))
    )
    (comp (ref "U703")
      (value "MP2144GJ")
      (footprint "TSOT23-8_3x1.7mm")
      (description "IC SYNC STEP-DOWN SW 1.2MHZ 0.6V 2A 2.5-5.5V TSOT23-8")
      (libsource (lib "*") (part "MP2144GJ_TSOT23_8P"))
    )
    (comp (ref "U704")
      (value "RT9193")
      (footprint "sot23-5")
      (description "IC VREG LDO 3.3V 300MA SOT-23-5")
      (libsource (lib "*") (part "RT9193-33PB"))
    )
    (comp (ref "U705")
      (value "RT9169-18GVL")
      (footprint "SOT23-3")
      (description "IC VREG LDO 1.8V 100mA 2-6V SOT-23-3")
      (libsource (lib "") (part "RT9169_3P_1"))
    )
    (comp (ref "U706")
      (value "MP2159GJ")
      (footprint "TSOT23-8_3x1.7mm")
      (description "IC VREG SYNC SW 0.6V 1A 2.5-6V TSOT23-8")
      (libsource (lib "*") (part "MP2159GJ_8P"))
    )
    (comp (ref "U707")
      (value "UM1750S-00")
      (footprint "SOT23-5")
      (description "IC VREG LDO ADJ 1-5V 350mA 2.5-6V SOT23-5")
      (libsource (lib "*") (part "UM1750S-00_5P"))
    )
    (comp (ref "U708")
      (value "UM805RE")
      (footprint "SOT143")
      (description "IC VOLT MONITOR 2.63V VTH RST 1-5.5V SOT143")
      (libsource (lib "*") (part "UM805_4P"))
    )
  )
  (nets
    (net (code "1") (name "/ARM_SOC_PG") (class "Default")
      (node (ref "TP703") (pin "1") (pinfunction "TP_1") (pintype "passive"))
      (node (ref "U702") (pin "1") (pinfunction "PG_1") (pintype "open_collector"))
    )
    (net (code "2") (name "/DCDC_3V3_PG") (class "Default")
      (node (ref "C743") (pin "1") (pinfunction "1_1") (pintype "passive"))
      (node (ref "C744") (pin "1") (pinfunction "1_1") (pintype "passive"))
      (node (ref "C747") (pin "1") (pinfunction "1_1") (pintype "passive"))
      (node (ref "R710") (pin "2") (pinfunction "2_2") (pintype "passive"))
      (node (ref "R722") (pin "2") (pinfunction "2_2") (pintype "passive"))
      (node (ref "R726") (pin "2") (pinfunction "2_2") (pintype "passive"))
      (node (ref "R727") (pin "2") (pinfunction "2_2") (pintype "passive"))
      (node (ref "TP706") (pin "1") (pinfunction "TP_1") (pintype "passive"))
      (node (ref "U704") (pin "3") (pinfunction "EN_3") (pintype "passive"))
      (node (ref "U707") (pin "3") (pinfunction "~{SHDN}_3") (pintype "input"))
    )
    (net (code "3") (name "/DISCHG_EN") (class "Default")
      (node (ref "C736") (pin "1") (pinfunction "1_1") (pintype "passive"))
      (node (ref "C745") (pin "1") (pinfunction "1_1") (pintype "passive"))
      (node (ref "C746") (pin "1") (pinfunction "1_1") (pintype "passive"))
      (node (ref "Q705") (pin "2") (pinfunction "GATE_2") (pintype "input"))
      (node (ref "Q706") (pin "2") (pinfunction "GATE_2") (pintype "input"))
      (node (ref "Q707") (pin "2") (pinfunction "GATE_2") (pintype "input"))
      (node (ref "R740") (pin "1") (pinfunction "1_1") (pintype "passive"))
    )
    (net (code "4") (name "/DRAM_PG") (class "Default")
      (node (ref "TP710") (pin "1") (pinfunction "TP_1") (pintype "passive"))
      (node (ref "U706") (pin "1") (pinfunction "PG_1") (pintype "open_collector"))
    )
    (net (code "5") (name "DCDC_3V3") (class "Default")
      (node (ref "C721") (pin "1") (pinfunction "1_1") (pintype "passive"))
      (node (ref "C722") (pin "1") (pinfunction "1_1") (pintype "passive"))
      (node (ref "C741") (pin "1") (pinfunction "1_1") (pintype "passive"))
      (node (ref "C742") (pin "1") (pinfunction "1_1") (pintype "passive"))
      (node (ref "D701") (pin "1") (pinfunction "C_1") (pintype "passive"))
      (node (ref "R701") (pin "1") (pinfunction "1_1") (pintype "passive"))
      (node (ref "R703") (pin "1") (pinfunction "1_1") (pintype "passive"))
      (node (ref "R705") (pin "1") (pinfunction "1_1") (pintype "passive"))
      (node (ref "R727") (pin "1") (pinfunction "1_1") (pintype "passive"))
      (node (ref "R730") (pin "2") (pinfunction "2_2") (pintype "passive"))
      (node (ref "R731") (pin "1") (pinfunction "1_1") (pintype "passive"))
      (node (ref "R732") (pin "1") (pinfunction "1_1") (pintype "passive"))
      (node (ref "U705") (pin "3") (pinfunction "VIN_3") (pintype "input"))
    )
    (net (code "6") (name "DRAM_1V35") (class "Default")
      (node (ref "R728") (pin "2") (pinfunction "2_2") (pintype "passive"))
    )
    (net (code "7") (name "GND") (class "Default")
      (node (ref "C701") (pin "2") (pinfunction "2_2") (pintype "passive"))
      (node (ref "C702") (pin "2") (pinfunction "2_2") (pintype "passive"))
      (node (ref "C703") (pin "2") (pinfunction "2_2") (pintype "passive"))
      (node (ref "C704") (pin "2") (pinfunction "2_2") (pintype "passive"))
      (node (ref "C705") (pin "2") (pinfunction "2_2") (pintype "passive"))
      (node (ref "C706") (pin "2") (pinfunction "2_2") (pintype "passive"))
      (node (ref "C707") (pin "2") (pinfunction "2_2") (pintype "passive"))
      (node (ref "C708") (pin "2") (pinfunction "2_2") (pintype "passive"))
      (node (ref "C709") (pin "2") (pinfunction "2_2") (pintype "passive"))
      (node (ref "C710") (pin "2") (pinfunction "2_2") (pintype "passive"))
      (node (ref "C711") (pin "2") (pinfunction "2_2") (pintype "passive"))
      (node (ref "C712") (pin "2") (pinfunction "2_2") (pintype "passive"))
      (node (ref "C713") (pin "2") (pinfunction "2_2") (pintype "passive"))
      (node (ref "C714") (pin "2") (pinfunction "2_2") (pintype "passive"))
      (node (ref "C715") (pin "2") (pinfunction "2_2") (pintype "passive"))
      (node (ref "C716") (pin "2") (pinfunction "2_2") (pintype "passive"))
      (node (ref "C717") (pin "2") (pinfunction "2_2") (pintype "passive"))
      (node (ref "C718") (pin "2") (pinfunction "2_2") (pintype "passive"))
      (node (ref "C719") (pin "2") (pinfunction "2_2") (pintype "passive"))
      (node (ref "C720") (pin "2") (pinfunction "2_2") (pintype "passive"))
      (node (ref "C721") (pin "2") (pinfunction "2_2") (pintype "passive"))
      (node (ref "C722") (pin "2") (pinfunction "2_2") (pintype "passive"))
      (node (ref "C723") (pin "2") (pinfunction "2_2") (pintype "passive"))
      (node (ref "C724") (pin "2") (pinfunction "2_2") (pintype "passive"))
      (node (ref "C725") (pin "2") (pinfunction "2_2") (pintype "passive"))
      (node (ref "C726") (pin "2") (pinfunction "2_2") (pintype "passive"))
      (node (ref "C727") (pin "2") (pinfunction "2_2") (pintype "passive"))
      (node (ref "C728") (pin "2") (pinfunction "2_2") (pintype "passive"))
      (node (ref "C729") (pin "2") (pinfunction "2_2") (pintype "passive"))
      (node (ref "C730") (pin "2") (pinfunction "2_2") (pintype "passive"))
      (node (ref "C731") (pin "2") (pinfunction "2_2") (pintype "passive"))
      (node (ref "C732") (pin "2") (pinfunction "2_2") (pintype "passive"))
      (node (ref "C733") (pin "2") (pinfunction "2_2") (pintype "passive"))
      (node (ref "C735") (pin "2") (pinfunction "2_2") (pintype "passive"))
      (node (ref "C736") (pin "2") (pinfunction "2_2") (pintype "passive"))
      (node (ref "C737") (pin "2") (pinfunction "2_2") (pintype "passive"))
      (node (ref "C739") (pin "2") (pinfunction "2_2") (pintype "passive"))
      (node (ref "C740") (pin "2") (pinfunction "2_2") (pintype "passive"))
      (node (ref "C741") (pin "2") (pinfunction "2_2") (pintype "passive"))
      (node (ref "C742") (pin "2") (pinfunction "2_2") (pintype "passive"))
      (node (ref "C743") (pin "2") (pinfunction "2_2") (pintype "passive"))
      (node (ref "C744") (pin "2") (pinfunction "2_2") (pintype "passive"))
      (node (ref "C745") (pin "2") (pinfunction "2_2") (pintype "passive"))
      (node (ref "C746") (pin "2") (pinfunction "2_2") (pintype "passive"))
      (node (ref "C747") (pin "2") (pinfunction "2_2") (pintype "passive"))
      (node (ref "Q704") (pin "1") (pinfunction "SOURCE_1") (pintype "passive"))
      (node (ref "Q705") (pin "1") (pinfunction "SOURCE_1") (pintype "passive"))
      (node (ref "Q706") (pin "1") (pinfunction "SOURCE_1") (pintype "passive"))
      (node (ref "Q707") (pin "1") (pinfunction "SOURCE_1") (pintype "passive"))
      (node (ref "R713") (pin "2") (pinfunction "2_2") (pintype "passive"))
      (node (ref "R714") (pin "2") (pinfunction "2_2") (pintype "passive"))
      (node (ref "R715") (pin "2") (pinfunction "2_2") (pintype "passive"))
      (node (ref "R718") (pin "2") (pinfunction "2_2") (pintype "passive"))
      (node (ref "R723") (pin "2") (pinfunction "2_2") (pintype "passive"))
      (node (ref "R724") (pin "2") (pinfunction "2_2") (pintype "passive"))
      (node (ref "R725") (pin "2") (pinfunction "2_2") (pintype "passive"))
      (node (ref "R755") (pin "2") (pinfunction "2_2") (pintype "passive"))
      (node (ref "U701") (pin "1") (pinfunction "GND_1") (pintype "power_in"))
      (node (ref "U702") (pin "4") (pinfunction "PGND_4") (pintype "power_in"))
      (node (ref "U702") (pin "6") (pinfunction "AGND_6") (pintype "power_in"))
      (node (ref "U703") (pin "4") (pinfunction "PGND_4") (pintype "power_in"))
      (node (ref "U703") (pin "6") (pinfunction "AGND_6") (pintype "power_in"))
      (node (ref "U704") (pin "2") (pinfunction "GND_2") (pintype "passive"))
      (node (ref "U705") (pin "1") (pinfunction "GND_1") (pintype "power_in"))
      (node (ref "U706") (pin "4") (pinfunction "PGND_4") (pintype "power_in"))
      (node (ref "U706") (pin "6") (pinfunction "AGND_6") (pintype "power_in"))
      (node (ref "U707") (pin "2") (pinfunction "GND_2") (pintype "power_in"))
      (node (ref "U708") (pin "1") (pinfunction "GND_1") (pintype "power_in"))
    )
    (net (code "8") (name "GPIO_DVFS") (class "Default")
      (node (ref "Q702") (pin "2") (pinfunction "GATE_2") (pintype "input"))
      (node (ref "R715") (pin "1") (pinfunction "1_1") (pintype "passive"))
    )
    (net (code "9") (name "MX6_POR_B") (class "Default")
      (node (ref "R757") (pin "1") (pinfunction "1_1") (pintype "passive"))
    )
    (net (code "10") (name "NVCC_CSI") (class "Default")
      (node (ref "R703") (pin "2") (pinfunction "2_2") (pintype "passive"))
      (node (ref "R704") (pin "2") (pinfunction "2_2") (pintype "passive"))
    )
    (net (code "11") (name "NVCC_NAND") (class "Default")
      (node (ref "R701") (pin "2") (pinfunction "2_2") (pintype "passive"))
      (node (ref "R702") (pin "2") (pinfunction "2_2") (pintype "passive"))
    )
    (net (code "12") (name "NVCC_SD") (class "Default")
      (node (ref "C732") (pin "1") (pinfunction "1_1") (pintype "passive"))
      (node (ref "C733") (pin "1") (pinfunction "1_1") (pintype "passive"))
      (node (ref "R720") (pin "1") (pinfunction "1_1") (pintype "passive"))
      (node (ref "R721") (pin "1") (pinfunction "1_1") (pintype "passive"))
      (node (ref "R731") (pin "2") (pinfunction "2_2") (pintype "passive"))
      (node (ref "TP709") (pin "1") (pinfunction "TP_1") (pintype "passive"))
      (node (ref "U707") (pin "5") (pinfunction "OUT_5") (pintype "power_in"))
    )
    (net (code "13") (name "Net-(D702-A)") (class "Default")
      (node (ref "D702") (pin "2") (pinfunction "A_2") (pintype "passive"))
      (node (ref "D705") (pin "2") (pinfunction "A_2") (pintype "passive"))
      (node (ref "R758") (pin "1") (pinfunction "1_1") (pintype "passive"))
      (node (ref "U708") (pin "3") (pinfunction "~{MR}_3") (pintype "input"))
    )
    (net (code "14") (name "Net-(D702-C)") (class "Default")
      (node (ref "C739") (pin "1") (pinfunction "1_1") (pintype "passive"))
      (node (ref "D702") (pin "1") (pinfunction "C_1") (pintype "passive"))
      (node (ref "R757") (pin "2") (pinfunction "2_2") (pintype "passive"))
    )
    (net (code "15") (name "Net-(D705-C)") (class "Default")
      (node (ref "C738") (pin "2") (pinfunction "2_2") (pintype "passive"))
      (node (ref "D705") (pin "1") (pinfunction "C_1") (pintype "passive"))
      (node (ref "R755") (pin "1") (pinfunction "1_1") (pintype "passive"))
    )
    (net (code "16") (name "Net-(Q701-DRAIN)") (class "Default")
      (node (ref "Q701") (pin "3") (pinfunction "DRAIN_3") (pintype "passive"))
      (node (ref "R707") (pin "2") (pinfunction "2_2") (pintype "passive"))
    )
    (net (code "17") (name "Net-(Q701-SOURCE)") (class "Default")
      (node (ref "Q701") (pin "1") (pinfunction "SOURCE_1") (pintype "passive"))
      (node (ref "Q702") (pin "1") (pinfunction "SOURCE_1") (pintype "passive"))
      (node (ref "R706") (pin "2") (pinfunction "2_2") (pintype "passive"))
      (node (ref "R713") (pin "1") (pinfunction "1_1") (pintype "passive"))
      (node (ref "U702") (pin "7") (pinfunction "FB_7") (pintype "input"))
    )
    (net (code "18") (name "Net-(Q702-DRAIN)") (class "Default")
      (node (ref "Q702") (pin "3") (pinfunction "DRAIN_3") (pintype "passive"))
      (node (ref "R708") (pin "2") (pinfunction "2_2") (pintype "passive"))
    )
    (net (code "19") (name "Net-(Q703-DRAIN)") (class "Default")
      (node (ref "Q703") (pin "3") (pinfunction "DRAIN_3") (pintype "passive"))
      (node (ref "R721") (pin "2") (pinfunction "2_2") (pintype "passive"))
    )
    (net (code "20") (name "Net-(Q703-SOURCE)") (class "Default")
      (node (ref "Q703") (pin "1") (pinfunction "SOURCE_1") (pintype "passive"))
      (node (ref "R720") (pin "2") (pinfunction "2_2") (pintype "passive"))
      (node (ref "R724") (pin "1") (pinfunction "1_1") (pintype "passive"))
      (node (ref "U707") (pin "4") (pinfunction "FB_4") (pintype "input"))
    )
    (net (code "21") (name "Net-(Q704-DRAIN)") (class "Default")
      (node (ref "Q704") (pin "3") (pinfunction "DRAIN_3") (pintype "passive"))
      (node (ref "R735") (pin "2") (pinfunction "2_2") (pintype "passive"))
      (node (ref "R740") (pin "2") (pinfunction "2_2") (pintype "passive"))
    )
    (net (code "22") (name "Net-(Q705-DRAIN)") (class "Default")
      (node (ref "Q705") (pin "3") (pinfunction "DRAIN_3") (pintype "passive"))
      (node (ref "R734") (pin "2") (pinfunction "2_2") (pintype "passive"))
    )
    (net (code "23") (name "Net-(Q706-DRAIN)") (class "Default")
      (node (ref "Q706") (pin "3") (pinfunction "DRAIN_3") (pintype "passive"))
      (node (ref "R736") (pin "2") (pinfunction "2_2") (pintype "passive"))
    )
    (net (code "24") (name "Net-(Q707-DRAIN)") (class "Default")
      (node (ref "Q707") (pin "3") (pinfunction "DRAIN_3") (pintype "passive"))
      (node (ref "R737") (pin "2") (pinfunction "2_2") (pintype "passive"))
    )
    (net (code "25") (name "Net-(TP702-TP)") (class "Default")
      (node (ref "C705") (pin "1") (pinfunction "1_1") (pintype "passive"))
      (node (ref "C706") (pin "1") (pinfunction "1_1") (pintype "passive"))
      (node (ref "L702") (pin "2") (pinfunction "2_2") (pintype "passive"))
      (node (ref "R706") (pin "1") (pinfunction "1_1") (pintype "passive"))
      (node (ref "R707") (pin "1") (pinfunction "1_1") (pintype "passive"))
      (node (ref "R708") (pin "1") (pinfunction "1_1") (pintype "passive"))
      (node (ref "R729") (pin "1") (pinfunction "1_1") (pintype "passive"))
      (node (ref "R737") (pin "1") (pinfunction "1_1") (pintype "passive"))
      (node (ref "TP702") (pin "1") (pinfunction "TP_1") (pintype "passive"))
      (node (ref "U702") (pin "5") (pinfunction "OUT_5") (pintype "output"))
    )
    (net (code "26") (name "Net-(TP705-TP)") (class "Default")
      (node (ref "C714") (pin "1") (pinfunction "1_1") (pintype "passive"))
      (node (ref "C715") (pin "1") (pinfunction "1_1") (pintype "passive"))
      (node (ref "L701") (pin "2") (pinfunction "2_2") (pintype "passive"))
      (node (ref "R717") (pin "1") (pinfunction "1_1") (pintype "passive"))
      (node (ref "R730") (pin "1") (pinfunction "1_1") (pintype "passive"))
      (node (ref "R734") (pin "1") (pinfunction "1_1") (pintype "passive"))
      (node (ref "TP705") (pin "1") (pinfunction "TP_1") (pintype "passive"))
      (node (ref "U703") (pin "5") (pinfunction "OUT_5") (pintype "input"))
    )
    (net (code "27") (name "Net-(TP708-TP)") (class "Default")
      (node (ref "C727") (pin "1") (pinfunction "1_1") (pintype "passive"))
      (node (ref "C728") (pin "1") (pinfunction "1_1") (pintype "passive"))
      (node (ref "L703") (pin "2") (pinfunction "2_2") (pintype "passive"))
      (node (ref "R719") (pin "1") (pinfunction "1_1") (pintype "passive"))
      (node (ref "R728") (pin "1") (pinfunction "1_1") (pintype "passive"))
      (node (ref "R736") (pin "1") (pinfunction "1_1") (pintype "passive"))
      (node (ref "TP708") (pin "1") (pinfunction "TP_1") (pintype "passive"))
      (node (ref "U706") (pin "5") (pinfunction "OUT_5") (pintype "output"))
    )
    (net (code "28") (name "Net-(U702-EN)") (class "Default")
      (node (ref "C707") (pin "1") (pinfunction "1_1") (pintype "passive"))
      (node (ref "R710") (pin "1") (pinfunction "1_1") (pintype "passive"))
      (node (ref "U702") (pin "8") (pinfunction "EN_8") (pintype "input"))
    )
    (net (code "29") (name "Net-(U702-SW)") (class "Default")
      (node (ref "L702") (pin "1") (pinfunction "1_1") (pintype "passive"))
      (node (ref "U702") (pin "3") (pinfunction "SW_3") (pintype "output"))
    )
    (net (code "30") (name "Net-(U703-EN)") (class "Default")
      (node (ref "C737") (pin "1") (pinfunction "1_1") (pintype "passive"))
      (node (ref "R716") (pin "2") (pinfunction "2_2") (pintype "passive"))
      (node (ref "R733") (pin "1") (pinfunction "1_1") (pintype "passive"))
      (node (ref "R758") (pin "2") (pinfunction "2_2") (pintype "passive"))
      (node (ref "U703") (pin "8") (pinfunction "EN_8") (pintype "input"))
      (node (ref "U708") (pin "2") (pinfunction "~{RESET}_2") (pintype "open_collector"))
    )
    (net (code "31") (name "Net-(U703-FB)") (class "Default")
      (node (ref "R717") (pin "2") (pinfunction "2_2") (pintype "passive"))
      (node (ref "R718") (pin "1") (pinfunction "1_1") (pintype "passive"))
      (node (ref "U703") (pin "7") (pinfunction "FB_7") (pintype "input"))
    )
    (net (code "32") (name "Net-(U703-PG)") (class "Default")
      (node (ref "R726") (pin "1") (pinfunction "1_1") (pintype "passive"))
      (node (ref "U703") (pin "1") (pinfunction "PG_1") (pintype "open_collector"))
    )
    (net (code "33") (name "Net-(U703-SW)") (class "Default")
      (node (ref "L701") (pin "1") (pinfunction "1_1") (pintype "passive"))
      (node (ref "U703") (pin "3") (pinfunction "SW_3") (pintype "output"))
    )
    (net (code "34") (name "Net-(U704-BP)") (class "Default")
      (node (ref "C720") (pin "1") (pinfunction "1_1") (pintype "passive"))
      (node (ref "U704") (pin "4") (pinfunction "BP_4") (pintype "passive"))
    )
    (net (code "35") (name "Net-(U706-EN)") (class "Default")
      (node (ref "C735") (pin "1") (pinfunction "1_1") (pintype "passive"))
      (node (ref "R722") (pin "1") (pinfunction "1_1") (pintype "passive"))
      (node (ref "U706") (pin "8") (pinfunction "EN_8") (pintype "input"))
    )
    (net (code "36") (name "Net-(U706-FB)") (class "Default")
      (node (ref "R719") (pin "2") (pinfunction "2_2") (pintype "passive"))
      (node (ref "R723") (pin "1") (pinfunction "1_1") (pintype "passive"))
      (node (ref "U706") (pin "7") (pinfunction "FB_7") (pintype "input"))
    )
    (net (code "37") (name "Net-(U706-SW)") (class "Default")
      (node (ref "L703") (pin "1") (pinfunction "1_1") (pintype "passive"))
      (node (ref "U706") (pin "3") (pinfunction "SW_3") (pintype "output"))
    )
    (net (code "38") (name "PMIC_ON_REQ") (class "Default")
      (node (ref "Q704") (pin "2") (pinfunction "GATE_2") (pintype "input"))
      (node (ref "R733") (pin "2") (pinfunction "2_2") (pintype "passive"))
    )
    (net (code "39") (name "PMIC_STBY_REQ") (class "Default")
      (node (ref "Q701") (pin "2") (pinfunction "GATE_2") (pintype "passive"))
      (node (ref "R714") (pin "1") (pinfunction "1_1") (pintype "passive"))
    )
    (net (code "40") (name "SD1_VSELECT") (class "Default")
      (node (ref "Q703") (pin "2") (pinfunction "GATE_2") (pintype "input"))
      (node (ref "R725") (pin "1") (pinfunction "1_1") (pintype "passive"))
    )
    (net (code "41") (name "VDDA_ADC_3P3") (class "Default")
      (node (ref "R705") (pin "2") (pinfunction "2_2") (pintype "passive"))
      (node (ref "R709") (pin "2") (pinfunction "2_2") (pintype "passive"))
    )
    (net (code "42") (name "VDD_ARM_SOC_IN") (class "Default")
      (node (ref "R729") (pin "2") (pinfunction "2_2") (pintype "passive"))
    )
    (net (code "43") (name "VDD_HIGH_IN") (class "Default")
      (node (ref "R732") (pin "2") (pinfunction "2_2") (pintype "passive"))
    )
    (net (code "44") (name "VDD_SNVS_3V3") (class "Default")
      (node (ref "C709") (pin "1") (pinfunction "1_1") (pintype "passive"))
      (node (ref "C710") (pin "1") (pinfunction "1_1") (pintype "passive"))
      (node (ref "C740") (pin "1") (pinfunction "1_1") (pintype "passive"))
      (node (ref "R735") (pin "1") (pinfunction "1_1") (pintype "passive"))
      (node (ref "TP701") (pin "1") (pinfunction "TP_1") (pintype "passive"))
      (node (ref "U701") (pin "2") (pinfunction "VOUT_2") (pintype "power_in"))
      (node (ref "U708") (pin "4") (pinfunction "VCC_4") (pintype "power_in"))
    )
    (net (code "45") (name "VLDO_1V8") (class "Default")
      (node (ref "C723") (pin "1") (pinfunction "1_1") (pintype "passive"))
      (node (ref "C724") (pin "1") (pinfunction "1_1") (pintype "passive"))
      (node (ref "D701") (pin "2") (pinfunction "A_2") (pintype "passive"))
      (node (ref "R702") (pin "1") (pinfunction "1_1") (pintype "passive"))
      (node (ref "R704") (pin "1") (pinfunction "1_1") (pintype "passive"))
      (node (ref "TP707") (pin "1") (pinfunction "TP_1") (pintype "passive"))
      (node (ref "U705") (pin "2") (pinfunction "VOUT_2") (pintype "output"))
    )
    (net (code "46") (name "VLDO_3V3") (class "Default")
      (node (ref "C718") (pin "1") (pinfunction "1_1") (pintype "passive"))
      (node (ref "C719") (pin "1") (pinfunction "1_1") (pintype "passive"))
      (node (ref "R709") (pin "1") (pinfunction "1_1") (pintype "passive"))
      (node (ref "TP704") (pin "1") (pinfunction "TP_1") (pintype "passive"))
      (node (ref "U704") (pin "5") (pinfunction "VOUT_5") (pintype "passive"))
    )
    (net (code "47") (name "VSYS") (class "Default")
      (node (ref "C701") (pin "1") (pinfunction "1_1") (pintype "passive"))
      (node (ref "C702") (pin "1") (pinfunction "1_1") (pintype "passive"))
      (node (ref "C703") (pin "1") (pinfunction "1_1") (pintype "passive"))
      (node (ref "C704") (pin "1") (pinfunction "1_1") (pintype "passive"))
      (node (ref "C708") (pin "1") (pinfunction "1_1") (pintype "passive"))
      (node (ref "C711") (pin "1") (pinfunction "1_1") (pintype "passive"))
      (node (ref "C712") (pin "1") (pinfunction "1_1") (pintype "passive"))
      (node (ref "C713") (pin "1") (pinfunction "1_1") (pintype "passive"))
      (node (ref "C716") (pin "1") (pinfunction "1_1") (pintype "passive"))
      (node (ref "C717") (pin "1") (pinfunction "1_1") (pintype "passive"))
      (node (ref "C725") (pin "1") (pinfunction "1_1") (pintype "passive"))
      (node (ref "C726") (pin "1") (pinfunction "1_1") (pintype "passive"))
      (node (ref "C729") (pin "1") (pinfunction "1_1") (pintype "passive"))
      (node (ref "C730") (pin "1") (pinfunction "1_1") (pintype "passive"))
      (node (ref "C731") (pin "1") (pinfunction "1_1") (pintype "passive"))
      (node (ref "R716") (pin "1") (pinfunction "1_1") (pintype "passive"))
      (node (ref "U701") (pin "3") (pinfunction "VIN_3") (pintype "power_in"))
      (node (ref "U702") (pin "2") (pinfunction "VIN_2") (pintype "power_in"))
      (node (ref "U703") (pin "2") (pinfunction "VIN_2") (pintype "power_in"))
      (node (ref "U704") (pin "1") (pinfunction "VIN_1") (pintype "passive"))
      (node (ref "U706") (pin "2") (pinfunction "VIN_2") (pintype "power_in"))
      (node (ref "U707") (pin "1") (pinfunction "IN_1") (pintype "power_in"))
    )
    (net (code "48") (name "nWDOG") (class "Default")
      (node (ref "C738") (pin "1") (pinfunction "1_1") (pintype "passive"))
    )
  )
)
